# Sheet1.net
KiCad netlist of a schematic drawn in Altium Designer
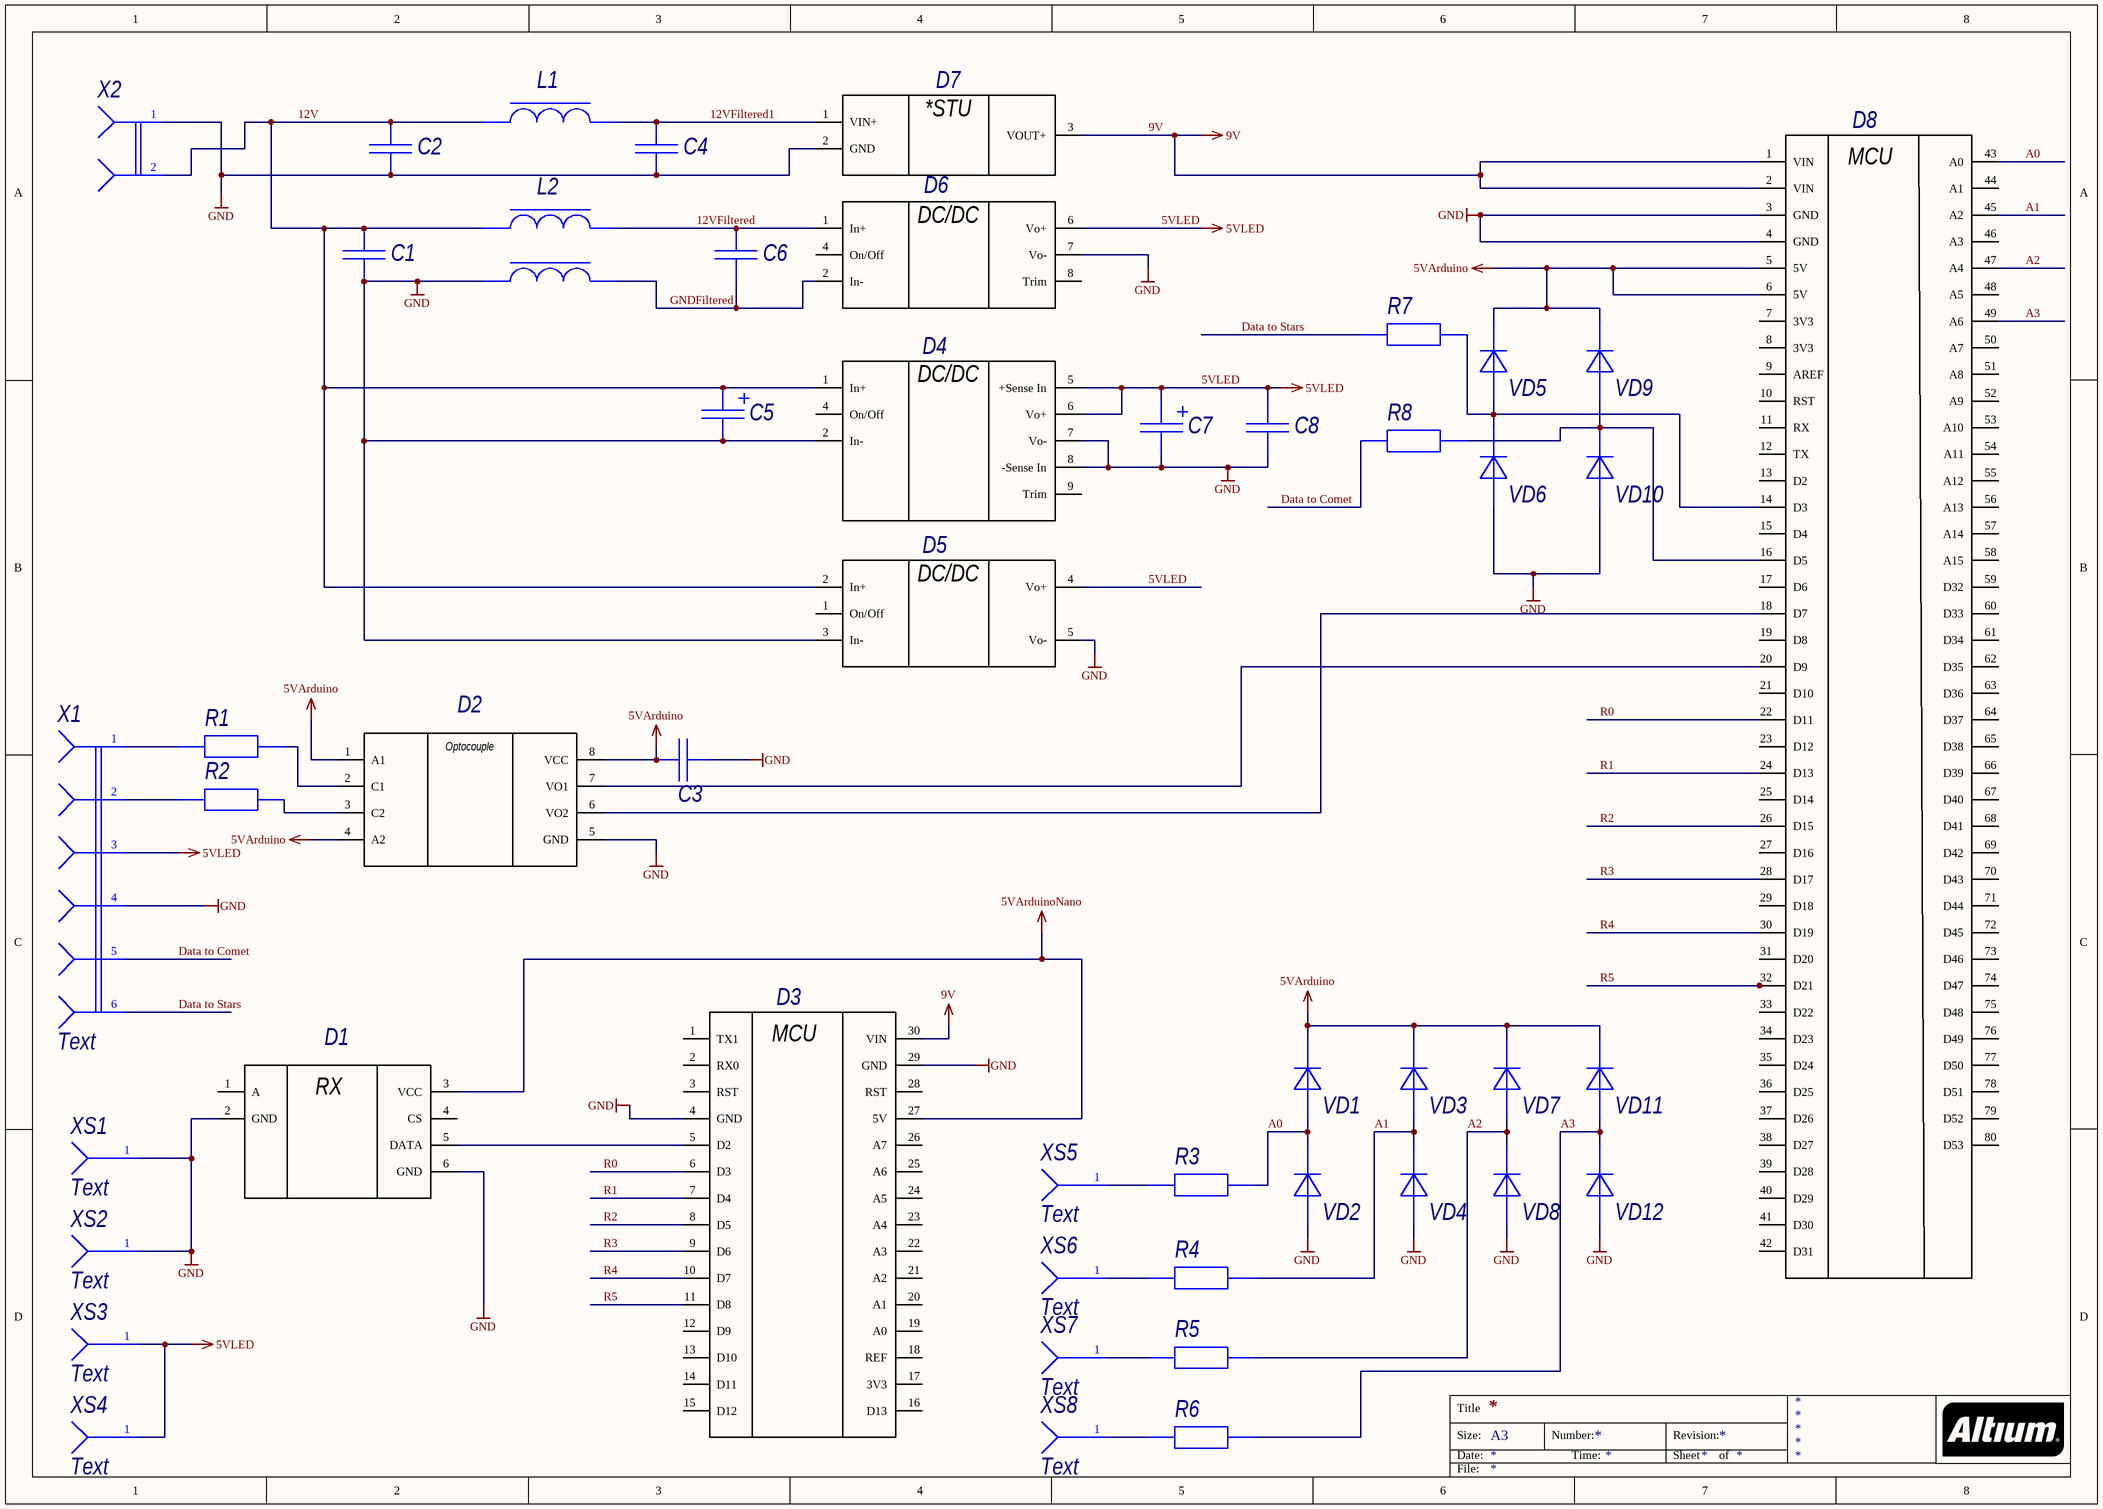
[diagram p0: Sheet1.SchDoc]

(export (version "E")
  (design (tool "Eeschema 10.0.6"))
  (components
    (comp (ref "C1")
      (value "Capacitor")
      (footprint "0805CAP")
      (fields (field (name "PUBLISHER") "Andrew Danich"))
      (libsource (lib "Capacitors") (part "Capacitor"))
    )
    (comp (ref "C2")
      (value "Capacitor")
      (footprint "0805CAP")
      (fields (field (name "PUBLISHER") "Andrew Danich"))
      (libsource (lib "Capacitors") (part "Capacitor"))
    )
    (comp (ref "C3")
      (value "Capacitor")
      (footprint "0805CAP")
      (fields (field (name "PUBLISHER") "Andrew Danich"))
      (libsource (lib "Capacitors") (part "Capacitor"))
    )
    (comp (ref "C4")
      (value "Capacitor")
      (footprint "0805CAP")
      (fields (field (name "PUBLISHER") "Andrew Danich"))
      (libsource (lib "Capacitors") (part "Capacitor"))
    )
    (comp (ref "C5")
      (value "Capacitor-Polar")
      (footprint "AL_CAP_D6.3L7.7")
      (fields (field (name "PUBLISHER") "Andrew Danich"))
      (libsource (lib "Capacitors") (part "Capacitor-Polar"))
    )
    (comp (ref "C6")
      (value "Capacitor")
      (footprint "0805CAP")
      (fields (field (name "PUBLISHER") "Andrew Danich"))
      (libsource (lib "Capacitors") (part "Capacitor"))
    )
    (comp (ref "C7")
      (value "Capacitor-Polar")
      (footprint "AL_CAP_d4l5.4")
      (fields (field (name "PUBLISHER") "Andrew Danich"))
      (libsource (lib "Capacitors") (part "Capacitor-Polar"))
    )
    (comp (ref "C8")
      (value "Capacitor")
      (footprint "0805CAP")
      (fields (field (name "PUBLISHER") "Andrew Danich"))
      (libsource (lib "Capacitors") (part "Capacitor"))
    )
    (comp (ref "D1")
      (value "SRX882")
      (footprint "SRX882")
      (fields (field (name "PUBLISHER") "Andrew Danich"))
      (libsource (lib "Boards") (part "SRX882"))
    )
    (comp (ref "D2")
      (value "HCPL-0631")
      (footprint "SOIC8")
      (fields (field (name "PUBLISHER") "Andrew Danich"))
      (libsource (lib "IC-Analog") (part "HCPL-0631"))
    )
    (comp (ref "D3")
      (value "Arduino Nano")
      (footprint "ARDUINO_NANO")
      (fields (field (name "PUBLISHER") "Andrew Danich"))
      (libsource (lib "Boards") (part "Arduino Nano"))
    )
    (comp (ref "D4")
      (value "UEI-5-10-Q12PR-C")
      (footprint "UEI50 Case C74")
      (fields (field (name "PUBLISHER") "Andrew Danich"))
      (libsource (lib "DC-DC Converters") (part "UEI-5-10-Q12PR-C"))
    )
    (comp (ref "D5")
      (value "МПА15")
      (footprint "МПА15")
      (fields (field (name "PUBLISHER") "Andrew Danich"))
      (libsource (lib "DC-DC Converters") (part "МПА15"))
    )
    (comp (ref "D6")
      (value "FDD25-05S1")
      (footprint "FDD25 50.8x50.8")
      (fields (field (name "PUBLISHER") "Andrew Danich"))
      (libsource (lib "DC-DC Converters") (part "FDD25-05S1"))
    )
    (comp (ref "D7")
      (value "R-78E9.0-0.5")
      (footprint "UL94V-0")
      (fields (field (name "PUBLISHER") "Andrew Danich"))
      (libsource (lib "DC-DC Converters") (part "R-78E9.0-0.5"))
    )
    (comp (ref "D8")
      (value "Arduino Mega 2560 Pro")
      (footprint "ARDUINO MEGA2560 PRO")
      (fields (field (name "PUBLISHER") "Andrew Danich"))
      (libsource (lib "Boards") (part "Arduino Mega 2560 Pro"))
    )
    (comp (ref "L1")
      (value "Coil")
      (footprint "1812")
      (fields (field (name "PUBLISHER") "Andrew Danich"))
      (libsource (lib "Coils") (part "Coil"))
    )
    (comp (ref "L2")
      (value "Common Mode Filter")
      (footprint "ACM7060")
      (fields (field (name "PUBLISHER") "Andrew Danich"))
      (libsource (lib "Coils") (part "Common Mode Filter"))
    )
    (comp (ref "R1")
      (value "Resistor")
      (footprint "0805")
      (fields (field (name "PUBLISHER") "Andrew Danich"))
      (libsource (lib "Resistors") (part "Resistor"))
    )
    (comp (ref "R2")
      (value "Resistor")
      (footprint "0805")
      (fields (field (name "PUBLISHER") "Andrew Danich"))
      (libsource (lib "Resistors") (part "Resistor"))
    )
    (comp (ref "R3")
      (value "Resistor")
      (footprint "0805")
      (fields (field (name "PUBLISHER") "Andrew Danich"))
      (libsource (lib "Resistors") (part "Resistor"))
    )
    (comp (ref "R4")
      (value "Resistor")
      (footprint "0805")
      (fields (field (name "PUBLISHER") "Andrew Danich"))
      (libsource (lib "Resistors") (part "Resistor"))
    )
    (comp (ref "R5")
      (value "Resistor")
      (footprint "0805")
      (fields (field (name "PUBLISHER") "Andrew Danich"))
      (libsource (lib "Resistors") (part "Resistor"))
    )
    (comp (ref "R6")
      (value "Resistor")
      (footprint "0805")
      (fields (field (name "PUBLISHER") "Andrew Danich"))
      (libsource (lib "Resistors") (part "Resistor"))
    )
    (comp (ref "R7")
      (value "Resistor")
      (footprint "0805")
      (fields (field (name "PUBLISHER") "Andrew Danich"))
      (libsource (lib "Resistors") (part "Resistor"))
    )
    (comp (ref "R8")
      (value "Resistor")
      (footprint "0805")
      (fields (field (name "PUBLISHER") "Andrew Danich"))
      (libsource (lib "Resistors") (part "Resistor"))
    )
    (comp (ref "VD1")
      (value "Diode")
      (footprint "SOD80")
      (fields (field (name "PUBLISHER") "Andrew Danich"))
      (libsource (lib "Diodes") (part "Diode"))
    )
    (comp (ref "VD2")
      (value "Diode")
      (footprint "SOD80")
      (fields (field (name "PUBLISHER") "Andrew Danich"))
      (libsource (lib "Diodes") (part "Diode"))
    )
    (comp (ref "VD3")
      (value "Diode")
      (footprint "SOD80")
      (fields (field (name "PUBLISHER") "Andrew Danich"))
      (libsource (lib "Diodes") (part "Diode"))
    )
    (comp (ref "VD4")
      (value "Diode")
      (footprint "SOD80")
      (fields (field (name "PUBLISHER") "Andrew Danich"))
      (libsource (lib "Diodes") (part "Diode"))
    )
    (comp (ref "VD5")
      (value "Diode")
      (footprint "SOD80")
      (fields (field (name "PUBLISHER") "Andrew Danich"))
      (libsource (lib "Diodes") (part "Diode"))
    )
    (comp (ref "VD6")
      (value "Diode")
      (footprint "SOD80")
      (fields (field (name "PUBLISHER") "Andrew Danich"))
      (libsource (lib "Diodes") (part "Diode"))
    )
    (comp (ref "VD7")
      (value "Diode")
      (footprint "SOD80")
      (fields (field (name "PUBLISHER") "Andrew Danich"))
      (libsource (lib "Diodes") (part "Diode"))
    )
    (comp (ref "VD8")
      (value "Diode")
      (footprint "SOD80")
      (fields (field (name "PUBLISHER") "Andrew Danich"))
      (libsource (lib "Diodes") (part "Diode"))
    )
    (comp (ref "VD9")
      (value "Diode")
      (footprint "SOD80")
      (fields (field (name "PUBLISHER") "Andrew Danich"))
      (libsource (lib "Diodes") (part "Diode"))
    )
    (comp (ref "VD10")
      (value "Diode")
      (footprint "SOD80")
      (fields (field (name "PUBLISHER") "Andrew Danich"))
      (libsource (lib "Diodes") (part "Diode"))
    )
    (comp (ref "VD11")
      (value "Diode")
      (footprint "SOD80")
      (fields (field (name "PUBLISHER") "Andrew Danich"))
      (libsource (lib "Diodes") (part "Diode"))
    )
    (comp (ref "VD12")
      (value "Diode")
      (footprint "SOD80")
      (fields (field (name "PUBLISHER") "Andrew Danich"))
      (libsource (lib "Diodes") (part "Diode"))
    )
    (comp (ref "X1")
      (value "Text")
      (footprint "DG142r-5.08-06p - duplicate")
      (fields (field (name "PUBLISHER") "Andrew Danich"))
      (libsource (lib "Connectors") (part "Con-6-F"))
    )
    (comp (ref "X2")
      (value "~")
      (footprint "DG142r-5.08-02p")
      (fields (field (name "PUBLISHER") "Andrew Danich"))
      (libsource (lib "Connectors") (part "Con-2-F"))
    )
    (comp (ref "XS1")
      (value "Text")
      (footprint "Through Hole 1 mm")
      (fields (field (name "PUBLISHER") "Andrew Danich"))
      (libsource (lib "Connectors") (part "Con-1-F"))
    )
    (comp (ref "XS2")
      (value "Text")
      (footprint "Through Hole 1 mm")
      (fields (field (name "PUBLISHER") "Andrew Danich"))
      (libsource (lib "Connectors") (part "Con-1-F"))
    )
    (comp (ref "XS3")
      (value "Text")
      (footprint "Through Hole 1 mm")
      (fields (field (name "PUBLISHER") "Andrew Danich"))
      (libsource (lib "Connectors") (part "Con-1-F"))
    )
    (comp (ref "XS4")
      (value "Text")
      (footprint "Through Hole 1 mm")
      (fields (field (name "PUBLISHER") "Andrew Danich"))
      (libsource (lib "Connectors") (part "Con-1-F"))
    )
    (comp (ref "XS5")
      (value "Text")
      (footprint "Through Hole 1 mm")
      (fields (field (name "PUBLISHER") "Andrew Danich"))
      (libsource (lib "Connectors") (part "Con-1-F"))
    )
    (comp (ref "XS6")
      (value "Text")
      (footprint "Through Hole 1 mm")
      (fields (field (name "PUBLISHER") "Andrew Danich"))
      (libsource (lib "Connectors") (part "Con-1-F"))
    )
    (comp (ref "XS7")
      (value "Text")
      (footprint "Through Hole 1 mm")
      (fields (field (name "PUBLISHER") "Andrew Danich"))
      (libsource (lib "Connectors") (part "Con-1-F"))
    )
    (comp (ref "XS8")
      (value "Text")
      (footprint "Through Hole 1 mm")
      (fields (field (name "PUBLISHER") "Andrew Danich"))
      (libsource (lib "Connectors") (part "Con-1-F"))
    )
  )
  (nets
    (net (code "1") (name "/12V") (class "Default")
      (node (ref "C1") (pin "2") (pinfunction "2_2") (pintype "passive"))
      (node (ref "C2") (pin "2") (pinfunction "2_2") (pintype "passive"))
      (node (ref "C5") (pin "1") (pinfunction "1_1") (pintype "passive"))
      (node (ref "D4") (pin "1") (pinfunction "In+_1") (pintype "power_in"))
      (node (ref "D5") (pin "2") (pinfunction "In+_2") (pintype "power_in"))
      (node (ref "L1") (pin "1") (pinfunction "1_1") (pintype "passive"))
      (node (ref "L2") (pin "1") (pinfunction "1_1") (pintype "passive"))
      (node (ref "X2") (pin "2") (pintype "passive"))
    )
    (net (code "2") (name "/12VFiltered") (class "Default")
      (node (ref "C6") (pin "2") (pinfunction "2_2") (pintype "passive"))
      (node (ref "D6") (pin "1") (pinfunction "In+_1") (pintype "power_in"))
      (node (ref "L2") (pin "4") (pinfunction "4_4") (pintype "passive"))
    )
    (net (code "3") (name "/12VFiltered1") (class "Default")
      (node (ref "C4") (pin "2") (pinfunction "2_2") (pintype "passive"))
      (node (ref "D7") (pin "1") (pinfunction "VIN+_1") (pintype "power_in"))
      (node (ref "L1") (pin "2") (pinfunction "2_2") (pintype "passive"))
    )
    (net (code "4") (name "/A0") (class "Default")
      (node (ref "D8") (pin "43") (pinfunction "A0_43") (pintype "power_in"))
      (node (ref "R3") (pin "2") (pinfunction "2_2") (pintype "passive"))
      (node (ref "VD1") (pin "1") (pinfunction "А_1") (pintype "passive"))
      (node (ref "VD2") (pin "2") (pinfunction "К_2") (pintype "passive"))
    )
    (net (code "5") (name "/A1") (class "Default")
      (node (ref "D8") (pin "45") (pinfunction "A2_45") (pintype "power_in"))
      (node (ref "R4") (pin "2") (pinfunction "2_2") (pintype "passive"))
      (node (ref "VD3") (pin "1") (pinfunction "А_1") (pintype "passive"))
      (node (ref "VD4") (pin "2") (pinfunction "К_2") (pintype "passive"))
    )
    (net (code "6") (name "/A2") (class "Default")
      (node (ref "D8") (pin "47") (pinfunction "A4_47") (pintype "power_in"))
      (node (ref "R5") (pin "2") (pinfunction "2_2") (pintype "passive"))
      (node (ref "VD7") (pin "1") (pinfunction "А_1") (pintype "passive"))
      (node (ref "VD8") (pin "2") (pinfunction "К_2") (pintype "passive"))
    )
    (net (code "7") (name "/A3") (class "Default")
      (node (ref "D8") (pin "49") (pinfunction "A6_49") (pintype "power_in"))
      (node (ref "R6") (pin "2") (pinfunction "2_2") (pintype "passive"))
      (node (ref "VD11") (pin "1") (pinfunction "А_1") (pintype "passive"))
      (node (ref "VD12") (pin "2") (pinfunction "К_2") (pintype "passive"))
    )
    (net (code "8") (name "/Data to Comet") (class "Default")
      (node (ref "R8") (pin "1") (pinfunction "1_1") (pintype "passive"))
      (node (ref "X1") (pin "5") (pintype "passive"))
    )
    (net (code "9") (name "/Data to Stars") (class "Default")
      (node (ref "R7") (pin "1") (pinfunction "1_1") (pintype "passive"))
      (node (ref "X1") (pin "6") (pintype "passive"))
    )
    (net (code "10") (name "/GNDFiltered") (class "Default")
      (node (ref "C6") (pin "1") (pinfunction "1_1") (pintype "passive"))
      (node (ref "D6") (pin "2") (pinfunction "In-_2") (pintype "power_in"))
      (node (ref "L2") (pin "3") (pinfunction "3_3") (pintype "passive"))
    )
    (net (code "11") (name "/R0") (class "Default")
      (node (ref "D3") (pin "6") (pinfunction "D3_6") (pintype "power_in"))
      (node (ref "D8") (pin "22") (pinfunction "D11_22") (pintype "power_in"))
    )
    (net (code "12") (name "/R1") (class "Default")
      (node (ref "D3") (pin "7") (pinfunction "D4_7") (pintype "power_in"))
      (node (ref "D8") (pin "24") (pinfunction "D13_24") (pintype "power_in"))
    )
    (net (code "13") (name "/R2") (class "Default")
      (node (ref "D3") (pin "8") (pinfunction "D5_8") (pintype "power_in"))
      (node (ref "D8") (pin "26") (pinfunction "D15_26") (pintype "power_in"))
    )
    (net (code "14") (name "/R3") (class "Default")
      (node (ref "D3") (pin "9") (pinfunction "D6_9") (pintype "power_in"))
      (node (ref "D8") (pin "28") (pinfunction "D17_28") (pintype "power_in"))
    )
    (net (code "15") (name "/R4") (class "Default")
      (node (ref "D3") (pin "10") (pinfunction "D7_10") (pintype "power_in"))
      (node (ref "D8") (pin "30") (pinfunction "D19_30") (pintype "power_in"))
    )
    (net (code "16") (name "/R5") (class "Default")
      (node (ref "D3") (pin "11") (pinfunction "D8_11") (pintype "power_in"))
      (node (ref "D8") (pin "32") (pinfunction "D21_32") (pintype "power_in"))
    )
    (net (code "17") (name "5VArduino") (class "Default")
      (node (ref "C3") (pin "2") (pinfunction "2_2") (pintype "passive"))
      (node (ref "D2") (pin "1") (pinfunction "A1_1") (pintype "power_in"))
      (node (ref "D2") (pin "4") (pinfunction "A2_4") (pintype "power_in"))
      (node (ref "D2") (pin "8") (pinfunction "VCC_8") (pintype "power_in"))
      (node (ref "D8") (pin "5") (pinfunction "5V_5") (pintype "power_in"))
      (node (ref "D8") (pin "6") (pinfunction "5V_6") (pintype "power_in"))
      (node (ref "VD1") (pin "2") (pinfunction "К_2") (pintype "passive"))
      (node (ref "VD11") (pin "2") (pinfunction "К_2") (pintype "passive"))
      (node (ref "VD3") (pin "2") (pinfunction "К_2") (pintype "passive"))
      (node (ref "VD5") (pin "2") (pinfunction "К_2") (pintype "passive"))
      (node (ref "VD7") (pin "2") (pinfunction "К_2") (pintype "passive"))
      (node (ref "VD9") (pin "2") (pinfunction "К_2") (pintype "passive"))
    )
    (net (code "18") (name "5VArduinoNano") (class "Default")
      (node (ref "D1") (pin "3") (pinfunction "VCC_3") (pintype "power_in"))
      (node (ref "D3") (pin "27") (pinfunction "5V_27") (pintype "power_in"))
    )
    (net (code "19") (name "5VLED") (class "Default")
      (node (ref "C7") (pin "1") (pinfunction "1_1") (pintype "passive"))
      (node (ref "C8") (pin "2") (pinfunction "2_2") (pintype "passive"))
      (node (ref "D4") (pin "5") (pinfunction "+Sense_In_5") (pintype "power_in"))
      (node (ref "D4") (pin "6") (pinfunction "Vo+_6") (pintype "power_in"))
      (node (ref "D5") (pin "4") (pinfunction "Vo+_4") (pintype "power_in"))
      (node (ref "D6") (pin "6") (pinfunction "Vo+_6") (pintype "power_in"))
      (node (ref "X1") (pin "3") (pintype "passive"))
      (node (ref "XS3") (pin "1") (pintype "passive"))
      (node (ref "XS4") (pin "1") (pintype "passive"))
    )
    (net (code "20") (name "9V") (class "Default")
      (node (ref "D3") (pin "30") (pinfunction "VIN_30") (pintype "power_in"))
      (node (ref "D7") (pin "3") (pinfunction "VOUT+_3") (pintype "power_in"))
      (node (ref "D8") (pin "1") (pinfunction "VIN_1") (pintype "power_in"))
      (node (ref "D8") (pin "2") (pinfunction "VIN_2") (pintype "power_in"))
    )
    (net (code "21") (name "GND") (class "Default")
      (node (ref "C1") (pin "1") (pinfunction "1_1") (pintype "passive"))
      (node (ref "C2") (pin "1") (pinfunction "1_1") (pintype "passive"))
      (node (ref "C3") (pin "1") (pinfunction "1_1") (pintype "passive"))
      (node (ref "C4") (pin "1") (pinfunction "1_1") (pintype "passive"))
      (node (ref "C5") (pin "2") (pinfunction "2_2") (pintype "passive"))
      (node (ref "C7") (pin "2") (pinfunction "2_2") (pintype "passive"))
      (node (ref "C8") (pin "1") (pinfunction "1_1") (pintype "passive"))
      (node (ref "D1") (pin "2") (pinfunction "GND_2") (pintype "power_in"))
      (node (ref "D1") (pin "6") (pinfunction "GND_6") (pintype "power_in"))
      (node (ref "D2") (pin "5") (pinfunction "GND_5") (pintype "power_in"))
      (node (ref "D3") (pin "29") (pinfunction "GND_29") (pintype "power_in"))
      (node (ref "D3") (pin "4") (pinfunction "GND_4") (pintype "power_in"))
      (node (ref "D4") (pin "2") (pinfunction "In-_2") (pintype "power_in"))
      (node (ref "D4") (pin "7") (pinfunction "Vo-_7") (pintype "power_in"))
      (node (ref "D4") (pin "8") (pinfunction "-Sense_In_8") (pintype "power_in"))
      (node (ref "D5") (pin "3") (pinfunction "In-_3") (pintype "power_in"))
      (node (ref "D5") (pin "5") (pinfunction "Vo-_5") (pintype "power_in"))
      (node (ref "D6") (pin "7") (pinfunction "Vo-_7") (pintype "power_in"))
      (node (ref "D7") (pin "2") (pinfunction "GND_2") (pintype "power_in"))
      (node (ref "D8") (pin "3") (pinfunction "GND_3") (pintype "power_in"))
      (node (ref "D8") (pin "4") (pinfunction "GND_4") (pintype "power_in"))
      (node (ref "L2") (pin "2") (pinfunction "2_2") (pintype "passive"))
      (node (ref "VD10") (pin "1") (pinfunction "А_1") (pintype "passive"))
      (node (ref "VD12") (pin "1") (pinfunction "А_1") (pintype "passive"))
      (node (ref "VD2") (pin "1") (pinfunction "А_1") (pintype "passive"))
      (node (ref "VD4") (pin "1") (pinfunction "А_1") (pintype "passive"))
      (node (ref "VD6") (pin "1") (pinfunction "А_1") (pintype "passive"))
      (node (ref "VD8") (pin "1") (pinfunction "А_1") (pintype "passive"))
      (node (ref "X1") (pin "4") (pintype "passive"))
      (node (ref "X2") (pin "1") (pintype "passive"))
      (node (ref "XS1") (pin "1") (pintype "passive"))
      (node (ref "XS2") (pin "1") (pintype "passive"))
    )
    (net (code "22") (name "Net-(D1-DATA)") (class "Default")
      (node (ref "D1") (pin "5") (pinfunction "DATA_5") (pintype "power_in"))
      (node (ref "D3") (pin "5") (pinfunction "D2_5") (pintype "power_in"))
    )
    (net (code "23") (name "Net-(D2-C1)") (class "Default")
      (node (ref "D2") (pin "2") (pinfunction "C1_2") (pintype "power_in"))
      (node (ref "R1") (pin "2") (pinfunction "2_2") (pintype "passive"))
    )
    (net (code "24") (name "Net-(D2-C2)") (class "Default")
      (node (ref "D2") (pin "3") (pinfunction "C2_3") (pintype "power_in"))
      (node (ref "R2") (pin "2") (pinfunction "2_2") (pintype "passive"))
    )
    (net (code "25") (name "Net-(D2-VO1)") (class "Default")
      (node (ref "D2") (pin "7") (pinfunction "VO1_7") (pintype "power_in"))
      (node (ref "D8") (pin "20") (pinfunction "D9_20") (pintype "power_in"))
    )
    (net (code "26") (name "Net-(D2-VO2)") (class "Default")
      (node (ref "D2") (pin "6") (pinfunction "VO2_6") (pintype "power_in"))
      (node (ref "D8") (pin "18") (pinfunction "D7_18") (pintype "power_in"))
    )
    (net (code "27") (name "Net-(D8-D3)") (class "Default")
      (node (ref "D8") (pin "14") (pinfunction "D3_14") (pintype "power_in"))
      (node (ref "R7") (pin "2") (pinfunction "2_2") (pintype "passive"))
      (node (ref "VD5") (pin "1") (pinfunction "А_1") (pintype "passive"))
      (node (ref "VD6") (pin "2") (pinfunction "К_2") (pintype "passive"))
    )
    (net (code "28") (name "Net-(D8-D5)") (class "Default")
      (node (ref "D8") (pin "16") (pinfunction "D5_16") (pintype "power_in"))
      (node (ref "R8") (pin "2") (pinfunction "2_2") (pintype "passive"))
      (node (ref "VD10") (pin "2") (pinfunction "К_2") (pintype "passive"))
      (node (ref "VD9") (pin "1") (pinfunction "А_1") (pintype "passive"))
    )
    (net (code "29") (name "Net-(R1-Pad1)") (class "Default")
      (node (ref "R1") (pin "1") (pinfunction "1_1") (pintype "passive"))
      (node (ref "X1") (pin "1") (pintype "passive"))
    )
    (net (code "30") (name "Net-(R2-Pad1)") (class "Default")
      (node (ref "R2") (pin "1") (pinfunction "1_1") (pintype "passive"))
      (node (ref "X1") (pin "2") (pintype "passive"))
    )
    (net (code "31") (name "Net-(R3-Pad1)") (class "Default")
      (node (ref "R3") (pin "1") (pinfunction "1_1") (pintype "passive"))
      (node (ref "XS5") (pin "1") (pintype "passive"))
    )
    (net (code "32") (name "Net-(R4-Pad1)") (class "Default")
      (node (ref "R4") (pin "1") (pinfunction "1_1") (pintype "passive"))
      (node (ref "XS6") (pin "1") (pintype "passive"))
    )
    (net (code "33") (name "Net-(R5-Pad1)") (class "Default")
      (node (ref "R5") (pin "1") (pinfunction "1_1") (pintype "passive"))
      (node (ref "XS7") (pin "1") (pintype "passive"))
    )
    (net (code "34") (name "Net-(R6-Pad1)") (class "Default")
      (node (ref "R6") (pin "1") (pinfunction "1_1") (pintype "passive"))
      (node (ref "XS8") (pin "1") (pintype "passive"))
    )
    (net (code "35") (name "unconnected-(D1-A-Pad1)") (class "Default")
      (node (ref "D1") (pin "1") (pinfunction "A_1") (pintype "power_in"))
    )
    (net (code "36") (name "unconnected-(D1-CS-Pad4)") (class "Default")
      (node (ref "D1") (pin "4") (pinfunction "CS_4") (pintype "power_in"))
    )
    (net (code "37") (name "unconnected-(D3-3V3-Pad17)") (class "Default")
      (node (ref "D3") (pin "17") (pinfunction "3V3_17") (pintype "power_in"))
    )
    (net (code "38") (name "unconnected-(D3-A0-Pad19)") (class "Default")
      (node (ref "D3") (pin "19") (pinfunction "A0_19") (pintype "power_in"))
    )
    (net (code "39") (name "unconnected-(D3-A1-Pad20)") (class "Default")
      (node (ref "D3") (pin "20") (pinfunction "A1_20") (pintype "power_in"))
    )
    (net (code "40") (name "unconnected-(D3-A2-Pad21)") (class "Default")
      (node (ref "D3") (pin "21") (pinfunction "A2_21") (pintype "power_in"))
    )
    (net (code "41") (name "unconnected-(D3-A3-Pad22)") (class "Default")
      (node (ref "D3") (pin "22") (pinfunction "A3_22") (pintype "power_in"))
    )
    (net (code "42") (name "unconnected-(D3-A4-Pad23)") (class "Default")
      (node (ref "D3") (pin "23") (pinfunction "A4_23") (pintype "power_in"))
    )
    (net (code "43") (name "unconnected-(D3-A5-Pad24)") (class "Default")
      (node (ref "D3") (pin "24") (pinfunction "A5_24") (pintype "power_in"))
    )
    (net (code "44") (name "unconnected-(D3-A6-Pad25)") (class "Default")
      (node (ref "D3") (pin "25") (pinfunction "A6_25") (pintype "power_in"))
    )
    (net (code "45") (name "unconnected-(D3-A7-Pad26)") (class "Default")
      (node (ref "D3") (pin "26") (pinfunction "A7_26") (pintype "power_in"))
    )
    (net (code "46") (name "unconnected-(D3-D9-Pad12)") (class "Default")
      (node (ref "D3") (pin "12") (pinfunction "D9_12") (pintype "power_in"))
    )
    (net (code "47") (name "unconnected-(D3-D10-Pad13)") (class "Default")
      (node (ref "D3") (pin "13") (pinfunction "D10_13") (pintype "power_in"))
    )
    (net (code "48") (name "unconnected-(D3-D11-Pad14)") (class "Default")
      (node (ref "D3") (pin "14") (pinfunction "D11_14") (pintype "power_in"))
    )
    (net (code "49") (name "unconnected-(D3-D12-Pad15)") (class "Default")
      (node (ref "D3") (pin "15") (pinfunction "D12_15") (pintype "power_in"))
    )
    (net (code "50") (name "unconnected-(D3-D13-Pad16)") (class "Default")
      (node (ref "D3") (pin "16") (pinfunction "D13_16") (pintype "power_in"))
    )
    (net (code "51") (name "unconnected-(D3-REF-Pad18)") (class "Default")
      (node (ref "D3") (pin "18") (pinfunction "REF_18") (pintype "power_in"))
    )
    (net (code "52") (name "unconnected-(D3-RST-Pad3)") (class "Default")
      (node (ref "D3") (pin "3") (pinfunction "RST_3") (pintype "power_in"))
    )
    (net (code "53") (name "unconnected-(D3-RST-Pad28)") (class "Default")
      (node (ref "D3") (pin "28") (pinfunction "RST_28") (pintype "power_in"))
    )
    (net (code "54") (name "unconnected-(D3-RX0-Pad2)") (class "Default")
      (node (ref "D3") (pin "2") (pinfunction "RX0_2") (pintype "power_in"))
    )
    (net (code "55") (name "unconnected-(D3-TX1-Pad1)") (class "Default")
      (node (ref "D3") (pin "1") (pinfunction "TX1_1") (pintype "power_in"))
    )
    (net (code "56") (name "unconnected-(D4-On{slash}Off-Pad4)") (class "Default")
      (node (ref "D4") (pin "4") (pinfunction "On/Off_4") (pintype "power_in"))
    )
    (net (code "57") (name "unconnected-(D4-Trim-Pad9)") (class "Default")
      (node (ref "D4") (pin "9") (pinfunction "Trim_9") (pintype "power_in"))
    )
    (net (code "58") (name "unconnected-(D5-On{slash}Off-Pad1)") (class "Default")
      (node (ref "D5") (pin "1") (pinfunction "On/Off_1") (pintype "power_in"))
    )
    (net (code "59") (name "unconnected-(D6-On{slash}Off-Pad4)") (class "Default")
      (node (ref "D6") (pin "4") (pinfunction "On/Off_4") (pintype "power_in"))
    )
    (net (code "60") (name "unconnected-(D6-Trim-Pad8)") (class "Default")
      (node (ref "D6") (pin "8") (pinfunction "Trim_8") (pintype "power_in"))
    )
    (net (code "61") (name "unconnected-(D8-3V3-Pad7)") (class "Default")
      (node (ref "D8") (pin "7") (pinfunction "3V3_7") (pintype "power_in"))
    )
    (net (code "62") (name "unconnected-(D8-3V3-Pad8)") (class "Default")
      (node (ref "D8") (pin "8") (pinfunction "3V3_8") (pintype "power_in"))
    )
    (net (code "63") (name "unconnected-(D8-A1-Pad44)") (class "Default")
      (node (ref "D8") (pin "44") (pinfunction "A1_44") (pintype "power_in"))
    )
    (net (code "64") (name "unconnected-(D8-A3-Pad46)") (class "Default")
      (node (ref "D8") (pin "46") (pinfunction "A3_46") (pintype "power_in"))
    )
    (net (code "65") (name "unconnected-(D8-A5-Pad48)") (class "Default")
      (node (ref "D8") (pin "48") (pinfunction "A5_48") (pintype "power_in"))
    )
    (net (code "66") (name "unconnected-(D8-A7-Pad50)") (class "Default")
      (node (ref "D8") (pin "50") (pinfunction "A7_50") (pintype "power_in"))
    )
    (net (code "67") (name "unconnected-(D8-A8-Pad51)") (class "Default")
      (node (ref "D8") (pin "51") (pinfunction "A8_51") (pintype "power_in"))
    )
    (net (code "68") (name "unconnected-(D8-A9-Pad52)") (class "Default")
      (node (ref "D8") (pin "52") (pinfunction "A9_52") (pintype "power_in"))
    )
    (net (code "69") (name "unconnected-(D8-A10-Pad53)") (class "Default")
      (node (ref "D8") (pin "53") (pinfunction "A10_53") (pintype "power_in"))
    )
    (net (code "70") (name "unconnected-(D8-A11-Pad54)") (class "Default")
      (node (ref "D8") (pin "54") (pinfunction "A11_54") (pintype "power_in"))
    )
    (net (code "71") (name "unconnected-(D8-A12-Pad55)") (class "Default")
      (node (ref "D8") (pin "55") (pinfunction "A12_55") (pintype "power_in"))
    )
    (net (code "72") (name "unconnected-(D8-A13-Pad56)") (class "Default")
      (node (ref "D8") (pin "56") (pinfunction "A13_56") (pintype "power_in"))
    )
    (net (code "73") (name "unconnected-(D8-A14-Pad57)") (class "Default")
      (node (ref "D8") (pin "57") (pinfunction "A14_57") (pintype "power_in"))
    )
    (net (code "74") (name "unconnected-(D8-A15-Pad58)") (class "Default")
      (node (ref "D8") (pin "58") (pinfunction "A15_58") (pintype "power_in"))
    )
    (net (code "75") (name "unconnected-(D8-AREF-Pad9)") (class "Default")
      (node (ref "D8") (pin "9") (pinfunction "AREF_9") (pintype "power_in"))
    )
    (net (code "76") (name "unconnected-(D8-D2-Pad13)") (class "Default")
      (node (ref "D8") (pin "13") (pinfunction "D2_13") (pintype "power_in"))
    )
    (net (code "77") (name "unconnected-(D8-D4-Pad15)") (class "Default")
      (node (ref "D8") (pin "15") (pinfunction "D4_15") (pintype "power_in"))
    )
    (net (code "78") (name "unconnected-(D8-D6-Pad17)") (class "Default")
      (node (ref "D8") (pin "17") (pinfunction "D6_17") (pintype "power_in"))
    )
    (net (code "79") (name "unconnected-(D8-D8-Pad19)") (class "Default")
      (node (ref "D8") (pin "19") (pinfunction "D8_19") (pintype "power_in"))
    )
    (net (code "80") (name "unconnected-(D8-D10-Pad21)") (class "Default")
      (node (ref "D8") (pin "21") (pinfunction "D10_21") (pintype "power_in"))
    )
    (net (code "81") (name "unconnected-(D8-D12-Pad23)") (class "Default")
      (node (ref "D8") (pin "23") (pinfunction "D12_23") (pintype "power_in"))
    )
    (net (code "82") (name "unconnected-(D8-D14-Pad25)") (class "Default")
      (node (ref "D8") (pin "25") (pinfunction "D14_25") (pintype "power_in"))
    )
    (net (code "83") (name "unconnected-(D8-D16-Pad27)") (class "Default")
      (node (ref "D8") (pin "27") (pinfunction "D16_27") (pintype "power_in"))
    )
    (net (code "84") (name "unconnected-(D8-D18-Pad29)") (class "Default")
      (node (ref "D8") (pin "29") (pinfunction "D18_29") (pintype "power_in"))
    )
    (net (code "85") (name "unconnected-(D8-D20-Pad31)") (class "Default")
      (node (ref "D8") (pin "31") (pinfunction "D20_31") (pintype "power_in"))
    )
    (net (code "86") (name "unconnected-(D8-D22-Pad33)") (class "Default")
      (node (ref "D8") (pin "33") (pinfunction "D22_33") (pintype "power_in"))
    )
    (net (code "87") (name "unconnected-(D8-D23-Pad34)") (class "Default")
      (node (ref "D8") (pin "34") (pinfunction "D23_34") (pintype "power_in"))
    )
    (net (code "88") (name "unconnected-(D8-D24-Pad35)") (class "Default")
      (node (ref "D8") (pin "35") (pinfunction "D24_35") (pintype "power_in"))
    )
    (net (code "89") (name "unconnected-(D8-D25-Pad36)") (class "Default")
      (node (ref "D8") (pin "36") (pinfunction "D25_36") (pintype "power_in"))
    )
    (net (code "90") (name "unconnected-(D8-D26-Pad37)") (class "Default")
      (node (ref "D8") (pin "37") (pinfunction "D26_37") (pintype "power_in"))
    )
    (net (code "91") (name "unconnected-(D8-D27-Pad38)") (class "Default")
      (node (ref "D8") (pin "38") (pinfunction "D27_38") (pintype "power_in"))
    )
    (net (code "92") (name "unconnected-(D8-D28-Pad39)") (class "Default")
      (node (ref "D8") (pin "39") (pinfunction "D28_39") (pintype "power_in"))
    )
    (net (code "93") (name "unconnected-(D8-D29-Pad40)") (class "Default")
      (node (ref "D8") (pin "40") (pinfunction "D29_40") (pintype "power_in"))
    )
    (net (code "94") (name "unconnected-(D8-D30-Pad41)") (class "Default")
      (node (ref "D8") (pin "41") (pinfunction "D30_41") (pintype "power_in"))
    )
    (net (code "95") (name "unconnected-(D8-D31-Pad42)") (class "Default")
      (node (ref "D8") (pin "42") (pinfunction "D31_42") (pintype "power_in"))
    )
    (net (code "96") (name "unconnected-(D8-D32-Pad59)") (class "Default")
      (node (ref "D8") (pin "59") (pinfunction "D32_59") (pintype "power_in"))
    )
    (net (code "97") (name "unconnected-(D8-D33-Pad60)") (class "Default")
      (node (ref "D8") (pin "60") (pinfunction "D33_60") (pintype "power_in"))
    )
    (net (code "98") (name "unconnected-(D8-D34-Pad61)") (class "Default")
      (node (ref "D8") (pin "61") (pinfunction "D34_61") (pintype "power_in"))
    )
    (net (code "99") (name "unconnected-(D8-D35-Pad62)") (class "Default")
      (node (ref "D8") (pin "62") (pinfunction "D35_62") (pintype "power_in"))
    )
    (net (code "100") (name "unconnected-(D8-D36-Pad63)") (class "Default")
      (node (ref "D8") (pin "63") (pinfunction "D36_63") (pintype "power_in"))
    )
    (net (code "101") (name "unconnected-(D8-D37-Pad64)") (class "Default")
      (node (ref "D8") (pin "64") (pinfunction "D37_64") (pintype "power_in"))
    )
    (net (code "102") (name "unconnected-(D8-D38-Pad65)") (class "Default")
      (node (ref "D8") (pin "65") (pinfunction "D38_65") (pintype "power_in"))
    )
    (net (code "103") (name "unconnected-(D8-D39-Pad66)") (class "Default")
      (node (ref "D8") (pin "66") (pinfunction "D39_66") (pintype "power_in"))
    )
    (net (code "104") (name "unconnected-(D8-D40-Pad67)") (class "Default")
      (node (ref "D8") (pin "67") (pinfunction "D40_67") (pintype "power_in"))
    )
    (net (code "105") (name "unconnected-(D8-D41-Pad68)") (class "Default")
      (node (ref "D8") (pin "68") (pinfunction "D41_68") (pintype "power_in"))
    )
    (net (code "106") (name "unconnected-(D8-D42-Pad69)") (class "Default")
      (node (ref "D8") (pin "69") (pinfunction "D42_69") (pintype "power_in"))
    )
    (net (code "107") (name "unconnected-(D8-D43-Pad70)") (class "Default")
      (node (ref "D8") (pin "70") (pinfunction "D43_70") (pintype "power_in"))
    )
    (net (code "108") (name "unconnected-(D8-D44-Pad71)") (class "Default")
      (node (ref "D8") (pin "71") (pinfunction "D44_71") (pintype "power_in"))
    )
    (net (code "109") (name "unconnected-(D8-D45-Pad72)") (class "Default")
      (node (ref "D8") (pin "72") (pinfunction "D45_72") (pintype "power_in"))
    )
    (net (code "110") (name "unconnected-(D8-D46-Pad73)") (class "Default")
      (node (ref "D8") (pin "73") (pinfunction "D46_73") (pintype "power_in"))
    )
    (net (code "111") (name "unconnected-(D8-D47-Pad74)") (class "Default")
      (node (ref "D8") (pin "74") (pinfunction "D47_74") (pintype "power_in"))
    )
    (net (code "112") (name "unconnected-(D8-D48-Pad75)") (class "Default")
      (node (ref "D8") (pin "75") (pinfunction "D48_75") (pintype "power_in"))
    )
    (net (code "113") (name "unconnected-(D8-D49-Pad76)") (class "Default")
      (node (ref "D8") (pin "76") (pinfunction "D49_76") (pintype "power_in"))
    )
    (net (code "114") (name "unconnected-(D8-D50-Pad77)") (class "Default")
      (node (ref "D8") (pin "77") (pinfunction "D50_77") (pintype "power_in"))
    )
    (net (code "115") (name "unconnected-(D8-D51-Pad78)") (class "Default")
      (node (ref "D8") (pin "78") (pinfunction "D51_78") (pintype "power_in"))
    )
    (net (code "116") (name "unconnected-(D8-D52-Pad79)") (class "Default")
      (node (ref "D8") (pin "79") (pinfunction "D52_79") (pintype "power_in"))
    )
    (net (code "117") (name "unconnected-(D8-D53-Pad80)") (class "Default")
      (node (ref "D8") (pin "80") (pinfunction "D53_80") (pintype "power_in"))
    )
    (net (code "118") (name "unconnected-(D8-RST-Pad10)") (class "Default")
      (node (ref "D8") (pin "10") (pinfunction "RST_10") (pintype "power_in"))
    )
    (net (code "119") (name "unconnected-(D8-RX-Pad11)") (class "Default")
      (node (ref "D8") (pin "11") (pinfunction "RX_11") (pintype "power_in"))
    )
    (net (code "120") (name "unconnected-(D8-TX-Pad12)") (class "Default")
      (node (ref "D8") (pin "12") (pinfunction "TX_12") (pintype "power_in"))
    )
  )
)
